# sensor_board.net
KiCad netlist of a schematic drawn in EasyEDA Pro
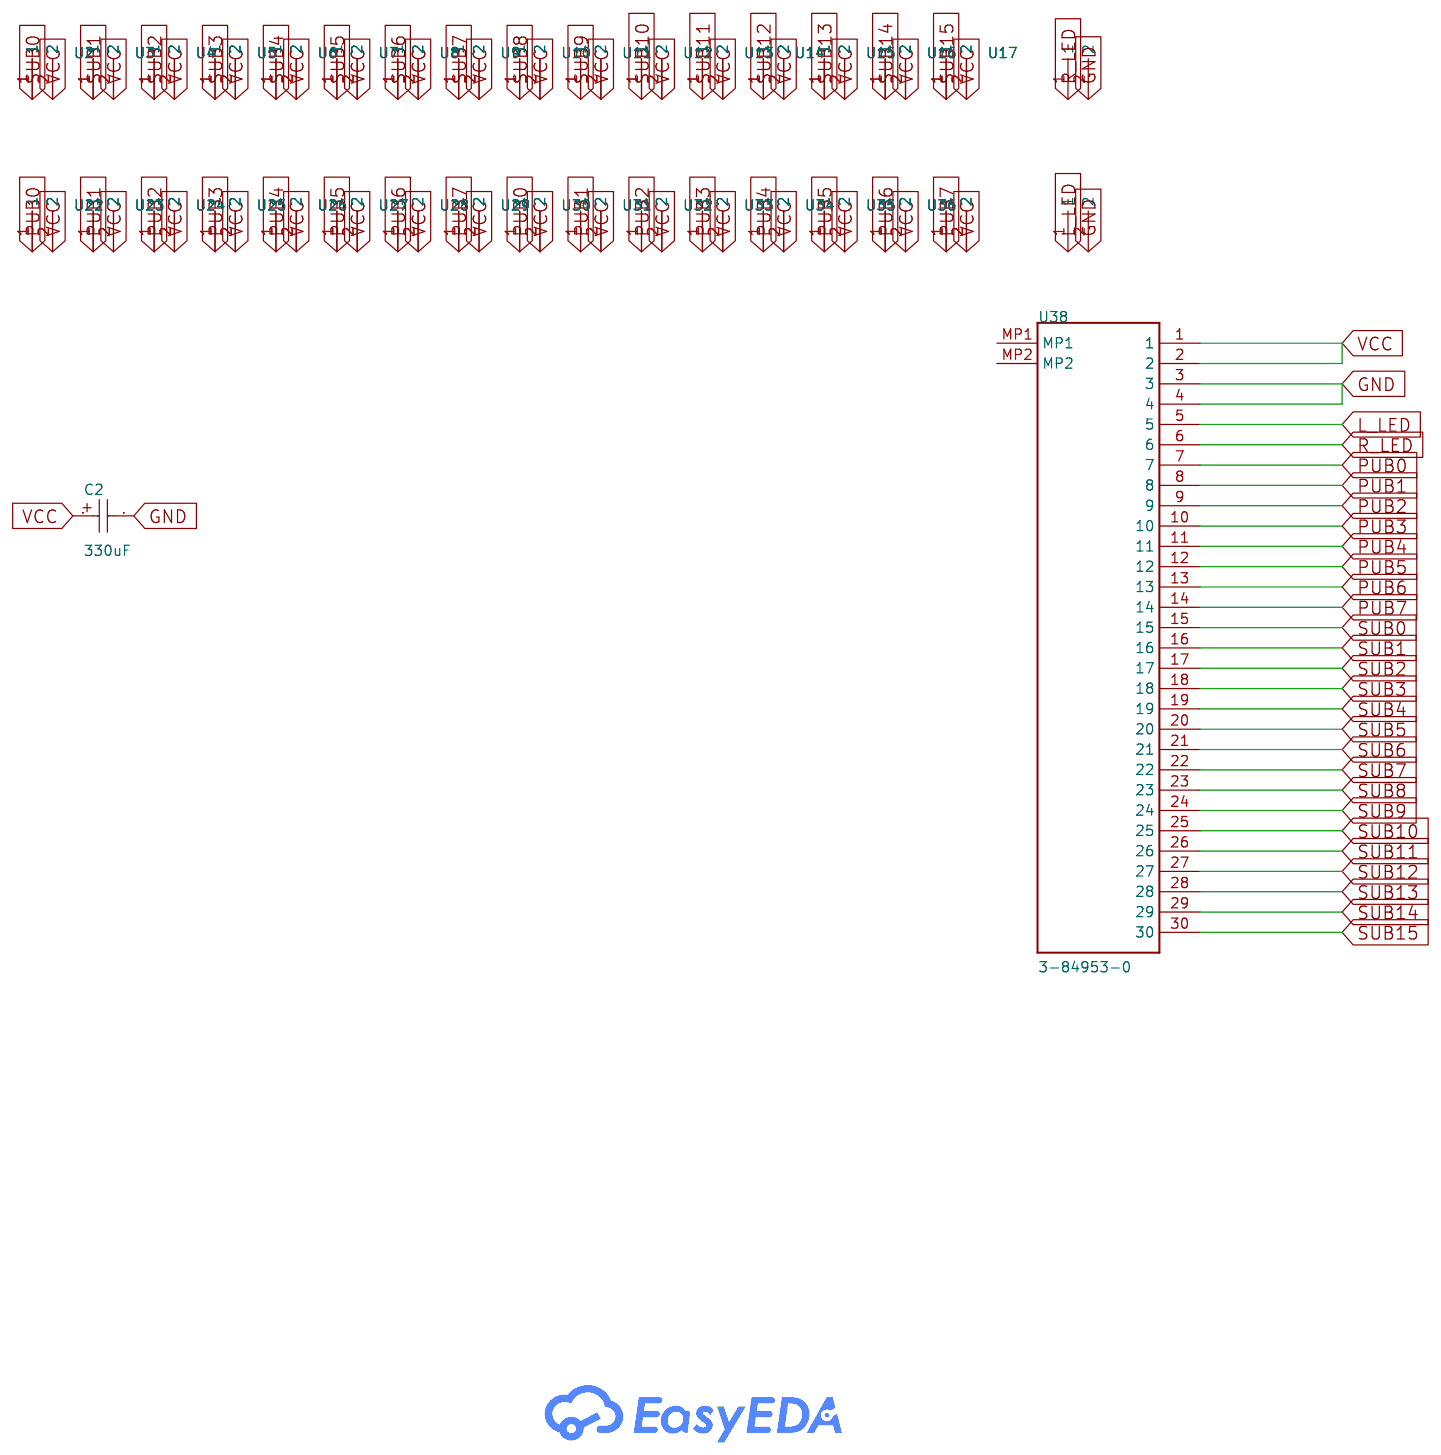
[diagram p0: schematic sheet]

(export (version "E")
  (design (tool "Eeschema 10.0.6"))
  (components
    (comp (ref "C2")
      (value "330uF")
      (footprint "easyedapro:CASE-D_7343")
      (fields (field (name "Manufacturer Part") "TAJD337M006RNJ") (field (name "Manufacturer") "Kyocera AVX"))
      (libsource (lib "easyedapro") (part "TAJD337M006RNJ"))
    )
    (comp (ref "U2")
      (value "~")
      (footprint "easyedapro:pub_pin")
      (libsource (lib "easyedapro") (part "pub_pin"))
    )
    (comp (ref "U3")
      (value "~")
      (footprint "easyedapro:pub_pin")
      (libsource (lib "easyedapro") (part "pub_pin"))
    )
    (comp (ref "U4")
      (value "~")
      (footprint "easyedapro:pub_pin")
      (libsource (lib "easyedapro") (part "pub_pin"))
    )
    (comp (ref "U5")
      (value "~")
      (footprint "easyedapro:pub_pin")
      (libsource (lib "easyedapro") (part "pub_pin"))
    )
    (comp (ref "U6")
      (value "~")
      (footprint "easyedapro:pub_pin")
      (libsource (lib "easyedapro") (part "pub_pin"))
    )
    (comp (ref "U7")
      (value "~")
      (footprint "easyedapro:pub_pin")
      (libsource (lib "easyedapro") (part "pub_pin"))
    )
    (comp (ref "U8")
      (value "~")
      (footprint "easyedapro:pub_pin")
      (libsource (lib "easyedapro") (part "pub_pin"))
    )
    (comp (ref "U9")
      (value "~")
      (footprint "easyedapro:pub_pin")
      (libsource (lib "easyedapro") (part "pub_pin"))
    )
    (comp (ref "U10")
      (value "~")
      (footprint "easyedapro:pub_pin")
      (libsource (lib "easyedapro") (part "pub_pin"))
    )
    (comp (ref "U11")
      (value "~")
      (footprint "easyedapro:pub_pin")
      (libsource (lib "easyedapro") (part "pub_pin"))
    )
    (comp (ref "U12")
      (value "~")
      (footprint "easyedapro:pub_pin")
      (libsource (lib "easyedapro") (part "pub_pin"))
    )
    (comp (ref "U13")
      (value "~")
      (footprint "easyedapro:pub_pin")
      (libsource (lib "easyedapro") (part "pub_pin"))
    )
    (comp (ref "U14")
      (value "~")
      (footprint "easyedapro:pub_pin")
      (libsource (lib "easyedapro") (part "pub_pin"))
    )
    (comp (ref "U15")
      (value "~")
      (footprint "easyedapro:pub_pin")
      (libsource (lib "easyedapro") (part "pub_pin"))
    )
    (comp (ref "U16")
      (value "~")
      (footprint "easyedapro:pub_pin")
      (libsource (lib "easyedapro") (part "pub_pin"))
    )
    (comp (ref "U17")
      (value "~")
      (footprint "easyedapro:pub_pin")
      (libsource (lib "easyedapro") (part "pub_pin"))
    )
    (comp (ref "U18")
      (value "~")
      (footprint "easyedapro:pub_pin")
      (libsource (lib "easyedapro") (part "pub_pin"))
    )
    (comp (ref "U21")
      (value "~")
      (footprint "easyedapro:pub_pin")
      (libsource (lib "easyedapro") (part "pub_pin"))
    )
    (comp (ref "U22")
      (value "~")
      (footprint "easyedapro:pub_pin")
      (libsource (lib "easyedapro") (part "pub_pin"))
    )
    (comp (ref "U23")
      (value "~")
      (footprint "easyedapro:pub_pin")
      (libsource (lib "easyedapro") (part "pub_pin"))
    )
    (comp (ref "U24")
      (value "~")
      (footprint "easyedapro:pub_pin")
      (libsource (lib "easyedapro") (part "pub_pin"))
    )
    (comp (ref "U25")
      (value "~")
      (footprint "easyedapro:pub_pin")
      (libsource (lib "easyedapro") (part "pub_pin"))
    )
    (comp (ref "U26")
      (value "~")
      (footprint "easyedapro:pub_pin")
      (libsource (lib "easyedapro") (part "pub_pin"))
    )
    (comp (ref "U27")
      (value "~")
      (footprint "easyedapro:pub_pin")
      (libsource (lib "easyedapro") (part "pub_pin"))
    )
    (comp (ref "U28")
      (value "~")
      (footprint "easyedapro:pub_pin")
      (libsource (lib "easyedapro") (part "pub_pin"))
    )
    (comp (ref "U29")
      (value "~")
      (footprint "easyedapro:pub_pin")
      (libsource (lib "easyedapro") (part "pub_pin"))
    )
    (comp (ref "U30")
      (value "~")
      (footprint "easyedapro:pub_pin")
      (libsource (lib "easyedapro") (part "pub_pin"))
    )
    (comp (ref "U31")
      (value "~")
      (footprint "easyedapro:pub_pin")
      (libsource (lib "easyedapro") (part "pub_pin"))
    )
    (comp (ref "U32")
      (value "~")
      (footprint "easyedapro:pub_pin")
      (libsource (lib "easyedapro") (part "pub_pin"))
    )
    (comp (ref "U33")
      (value "~")
      (footprint "easyedapro:pub_pin")
      (libsource (lib "easyedapro") (part "pub_pin"))
    )
    (comp (ref "U34")
      (value "~")
      (footprint "easyedapro:pub_pin")
      (libsource (lib "easyedapro") (part "pub_pin"))
    )
    (comp (ref "U35")
      (value "~")
      (footprint "easyedapro:pub_pin")
      (libsource (lib "easyedapro") (part "pub_pin"))
    )
    (comp (ref "U36")
      (value "~")
      (footprint "easyedapro:pub_pin")
      (libsource (lib "easyedapro") (part "pub_pin"))
    )
    (comp (ref "U37")
      (value "~")
      (footprint "easyedapro:pub_pin")
      (libsource (lib "easyedapro") (part "pub_pin"))
    )
    (comp (ref "U38")
      (value "3-84953-0")
      (footprint "easyedapro:3849530")
      (libsource (lib "easyedapro") (part "3-84953-0"))
    )
  )
  (nets
    (net (code "1") (name "GND") (class "Default")
      (node (ref "C2") (pin "2") (pinfunction "2_2") (pintype "input"))
      (node (ref "U18") (pin "2") (pinfunction "2_2") (pintype "input"))
      (node (ref "U21") (pin "2") (pinfunction "2_2") (pintype "input"))
      (node (ref "U38") (pin "3") (pinfunction "3_3") (pintype "bidirectional"))
      (node (ref "U38") (pin "4") (pinfunction "4_4") (pintype "bidirectional"))
    )
    (net (code "2") (name "L_LED") (class "Default")
      (node (ref "U21") (pin "1") (pinfunction "1_1") (pintype "input"))
      (node (ref "U38") (pin "5") (pinfunction "5_5") (pintype "bidirectional"))
    )
    (net (code "3") (name "PUB0") (class "Default")
      (node (ref "U22") (pin "1") (pinfunction "1_1") (pintype "input"))
      (node (ref "U30") (pin "1") (pinfunction "1_1") (pintype "input"))
      (node (ref "U38") (pin "7") (pinfunction "7_7") (pintype "bidirectional"))
    )
    (net (code "4") (name "PUB1") (class "Default")
      (node (ref "U23") (pin "1") (pinfunction "1_1") (pintype "input"))
      (node (ref "U31") (pin "1") (pinfunction "1_1") (pintype "input"))
      (node (ref "U38") (pin "8") (pinfunction "8_8") (pintype "bidirectional"))
    )
    (net (code "5") (name "PUB2") (class "Default")
      (node (ref "U24") (pin "1") (pinfunction "1_1") (pintype "input"))
      (node (ref "U32") (pin "1") (pinfunction "1_1") (pintype "input"))
      (node (ref "U38") (pin "9") (pinfunction "9_9") (pintype "bidirectional"))
    )
    (net (code "6") (name "PUB3") (class "Default")
      (node (ref "U25") (pin "1") (pinfunction "1_1") (pintype "input"))
      (node (ref "U33") (pin "1") (pinfunction "1_1") (pintype "input"))
      (node (ref "U38") (pin "10") (pinfunction "10_10") (pintype "bidirectional"))
    )
    (net (code "7") (name "PUB4") (class "Default")
      (node (ref "U26") (pin "1") (pinfunction "1_1") (pintype "input"))
      (node (ref "U34") (pin "1") (pinfunction "1_1") (pintype "input"))
      (node (ref "U38") (pin "11") (pinfunction "11_11") (pintype "bidirectional"))
    )
    (net (code "8") (name "PUB5") (class "Default")
      (node (ref "U27") (pin "1") (pinfunction "1_1") (pintype "input"))
      (node (ref "U35") (pin "1") (pinfunction "1_1") (pintype "input"))
      (node (ref "U38") (pin "12") (pinfunction "12_12") (pintype "bidirectional"))
    )
    (net (code "9") (name "PUB6") (class "Default")
      (node (ref "U28") (pin "1") (pinfunction "1_1") (pintype "input"))
      (node (ref "U36") (pin "1") (pinfunction "1_1") (pintype "input"))
      (node (ref "U38") (pin "13") (pinfunction "13_13") (pintype "bidirectional"))
    )
    (net (code "10") (name "PUB7") (class "Default")
      (node (ref "U29") (pin "1") (pinfunction "1_1") (pintype "input"))
      (node (ref "U37") (pin "1") (pinfunction "1_1") (pintype "input"))
      (node (ref "U38") (pin "14") (pinfunction "14_14") (pintype "bidirectional"))
    )
    (net (code "11") (name "R_LED") (class "Default")
      (node (ref "U18") (pin "1") (pinfunction "1_1") (pintype "input"))
      (node (ref "U38") (pin "6") (pinfunction "6_6") (pintype "bidirectional"))
    )
    (net (code "12") (name "SUB0") (class "Default")
      (node (ref "U2") (pin "1") (pinfunction "1_1") (pintype "input"))
      (node (ref "U38") (pin "15") (pinfunction "15_15") (pintype "bidirectional"))
    )
    (net (code "13") (name "SUB1") (class "Default")
      (node (ref "U3") (pin "1") (pinfunction "1_1") (pintype "input"))
      (node (ref "U38") (pin "16") (pinfunction "16_16") (pintype "bidirectional"))
    )
    (net (code "14") (name "SUB2") (class "Default")
      (node (ref "U38") (pin "17") (pinfunction "17_17") (pintype "bidirectional"))
      (node (ref "U4") (pin "1") (pinfunction "1_1") (pintype "input"))
    )
    (net (code "15") (name "SUB3") (class "Default")
      (node (ref "U38") (pin "18") (pinfunction "18_18") (pintype "bidirectional"))
      (node (ref "U5") (pin "1") (pinfunction "1_1") (pintype "input"))
    )
    (net (code "16") (name "SUB4") (class "Default")
      (node (ref "U38") (pin "19") (pinfunction "19_19") (pintype "bidirectional"))
      (node (ref "U6") (pin "1") (pinfunction "1_1") (pintype "input"))
    )
    (net (code "17") (name "SUB5") (class "Default")
      (node (ref "U38") (pin "20") (pinfunction "20_20") (pintype "bidirectional"))
      (node (ref "U7") (pin "1") (pinfunction "1_1") (pintype "input"))
    )
    (net (code "18") (name "SUB6") (class "Default")
      (node (ref "U38") (pin "21") (pinfunction "21_21") (pintype "bidirectional"))
      (node (ref "U8") (pin "1") (pinfunction "1_1") (pintype "input"))
    )
    (net (code "19") (name "SUB7") (class "Default")
      (node (ref "U38") (pin "22") (pinfunction "22_22") (pintype "bidirectional"))
      (node (ref "U9") (pin "1") (pinfunction "1_1") (pintype "input"))
    )
    (net (code "20") (name "SUB8") (class "Default")
      (node (ref "U10") (pin "1") (pinfunction "1_1") (pintype "input"))
      (node (ref "U38") (pin "23") (pinfunction "23_23") (pintype "bidirectional"))
    )
    (net (code "21") (name "SUB9") (class "Default")
      (node (ref "U11") (pin "1") (pinfunction "1_1") (pintype "input"))
      (node (ref "U38") (pin "24") (pinfunction "24_24") (pintype "bidirectional"))
    )
    (net (code "22") (name "SUB10") (class "Default")
      (node (ref "U12") (pin "1") (pinfunction "1_1") (pintype "input"))
      (node (ref "U38") (pin "25") (pinfunction "25_25") (pintype "bidirectional"))
    )
    (net (code "23") (name "SUB11") (class "Default")
      (node (ref "U13") (pin "1") (pinfunction "1_1") (pintype "input"))
      (node (ref "U38") (pin "26") (pinfunction "26_26") (pintype "bidirectional"))
    )
    (net (code "24") (name "SUB12") (class "Default")
      (node (ref "U14") (pin "1") (pinfunction "1_1") (pintype "input"))
      (node (ref "U38") (pin "27") (pinfunction "27_27") (pintype "bidirectional"))
    )
    (net (code "25") (name "SUB13") (class "Default")
      (node (ref "U15") (pin "1") (pinfunction "1_1") (pintype "input"))
      (node (ref "U38") (pin "28") (pinfunction "28_28") (pintype "bidirectional"))
    )
    (net (code "26") (name "SUB14") (class "Default")
      (node (ref "U16") (pin "1") (pinfunction "1_1") (pintype "input"))
      (node (ref "U38") (pin "29") (pinfunction "29_29") (pintype "bidirectional"))
    )
    (net (code "27") (name "SUB15") (class "Default")
      (node (ref "U17") (pin "1") (pinfunction "1_1") (pintype "input"))
      (node (ref "U38") (pin "30") (pinfunction "30_30") (pintype "bidirectional"))
    )
    (net (code "28") (name "VCC") (class "Default")
      (node (ref "C2") (pin "1") (pinfunction "1_1") (pintype "input"))
      (node (ref "U10") (pin "2") (pinfunction "2_2") (pintype "input"))
      (node (ref "U11") (pin "2") (pinfunction "2_2") (pintype "input"))
      (node (ref "U12") (pin "2") (pinfunction "2_2") (pintype "input"))
      (node (ref "U13") (pin "2") (pinfunction "2_2") (pintype "input"))
      (node (ref "U14") (pin "2") (pinfunction "2_2") (pintype "input"))
      (node (ref "U15") (pin "2") (pinfunction "2_2") (pintype "input"))
      (node (ref "U16") (pin "2") (pinfunction "2_2") (pintype "input"))
      (node (ref "U17") (pin "2") (pinfunction "2_2") (pintype "input"))
      (node (ref "U2") (pin "2") (pinfunction "2_2") (pintype "input"))
      (node (ref "U22") (pin "2") (pinfunction "2_2") (pintype "input"))
      (node (ref "U23") (pin "2") (pinfunction "2_2") (pintype "input"))
      (node (ref "U24") (pin "2") (pinfunction "2_2") (pintype "input"))
      (node (ref "U25") (pin "2") (pinfunction "2_2") (pintype "input"))
      (node (ref "U26") (pin "2") (pinfunction "2_2") (pintype "input"))
      (node (ref "U27") (pin "2") (pinfunction "2_2") (pintype "input"))
      (node (ref "U28") (pin "2") (pinfunction "2_2") (pintype "input"))
      (node (ref "U29") (pin "2") (pinfunction "2_2") (pintype "input"))
      (node (ref "U3") (pin "2") (pinfunction "2_2") (pintype "input"))
      (node (ref "U30") (pin "2") (pinfunction "2_2") (pintype "input"))
      (node (ref "U31") (pin "2") (pinfunction "2_2") (pintype "input"))
      (node (ref "U32") (pin "2") (pinfunction "2_2") (pintype "input"))
      (node (ref "U33") (pin "2") (pinfunction "2_2") (pintype "input"))
      (node (ref "U34") (pin "2") (pinfunction "2_2") (pintype "input"))
      (node (ref "U35") (pin "2") (pinfunction "2_2") (pintype "input"))
      (node (ref "U36") (pin "2") (pinfunction "2_2") (pintype "input"))
      (node (ref "U37") (pin "2") (pinfunction "2_2") (pintype "input"))
      (node (ref "U38") (pin "1") (pinfunction "1_1") (pintype "bidirectional"))
      (node (ref "U38") (pin "2") (pinfunction "2_2") (pintype "bidirectional"))
      (node (ref "U4") (pin "2") (pinfunction "2_2") (pintype "input"))
      (node (ref "U5") (pin "2") (pinfunction "2_2") (pintype "input"))
      (node (ref "U6") (pin "2") (pinfunction "2_2") (pintype "input"))
      (node (ref "U7") (pin "2") (pinfunction "2_2") (pintype "input"))
      (node (ref "U8") (pin "2") (pinfunction "2_2") (pintype "input"))
      (node (ref "U9") (pin "2") (pinfunction "2_2") (pintype "input"))
    )
    (net (code "29") (name "unconnected-(U38-PadMP1)") (class "Default")
      (node (ref "U38") (pin "MP1") (pinfunction "MP1_MP1") (pintype "bidirectional"))
    )
    (net (code "30") (name "unconnected-(U38-PadMP2)") (class "Default")
      (node (ref "U38") (pin "MP2") (pinfunction "MP2_MP2") (pintype "bidirectional"))
    )
  )
)
